# LM2596.net
KiCad netlist of a schematic drawn in Altium Designer
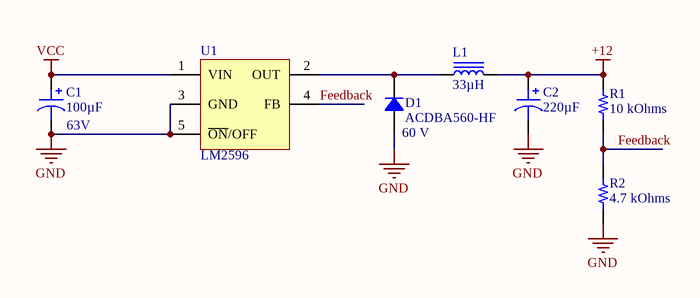
[diagram p0: LM2596.SchDoc]

(export (version "E")
  (design (tool "Eeschema 10.0.6"))
  (components
    (comp (ref "C1")
      (value "100µF")
      (footprint "CAP TH ALUM ELEC D8.00mm S3.50mm H12.50mm")
      (description "CAP ALUM 100UF 20% 63V RADIAL")
      (fields
        (field (name "PART NUMBER") "ECA-1JM101")
        (field (name "MANUFACTURER") "Panasonic Electronic Components")
        (field (name "VOLTAGE - RATED") "63V")
      )
      (libsource (lib "Celestial Altium Library - altium_library") (part "Polarised Capacitor"))
    )
    (comp (ref "C2")
      (value "220µF")
      (footprint "CAP TH ALUM ELEC D10.00mm S5.00mm H16.00mm")
      (description "CAP ALUM 220UF 20% 63V RADIAL")
      (fields (field (name "PART NUMBER") "UFW1J221MPD") (field (name "MANUFACTURER") "Nichicon"))
      (libsource (lib "Celestial Altium Library - altium_library") (part "Polarised Capacitor"))
    )
    (comp (ref "D1")
      (value "ACDBA560-HF")
      (footprint "DO214AC SMA")
      (description "DIODE SCHOTTKY 60V 5A DO214AC")
      (fields
        (field (name "MANUFACTURER") "Comchip Technology")
        (field (name "VOLTAGE - DC REVERSE (VR) (MAX)") "60 V")
      )
      (libsource (lib "Celestial Altium Library - altium_library") (part "Diode"))
    )
    (comp (ref "L1")
      (value "33µH")
      (footprint "BOURNS SRR1280")
      (description "FIXED IND 33UH 3.5A 57 MOHM SMD")
      (fields (field (name "PART NUMBER") "SRR1280-330M") (field (name "MANUFACTURER") "Bourns Inc."))
      (libsource (lib "Celestial Altium Library - altium_library") (part "Inductor"))
    )
    (comp (ref "R1")
      (value "10 kOhms")
      (footprint "RES 0805_2012")
      (description "RES 10K OHM 0.1% 1/10W 0805")
      (fields
        (field (name "PART NUMBER") "RNCS0805BKE10K0")
        (field (name "MANUFACTURER") "Stackpole Electronics Inc")
      )
      (libsource (lib "Celestial Altium Library - altium_library") (part "Resistor"))
    )
    (comp (ref "R2")
      (value "4.7 kOhms")
      (footprint "RES 0805_2012")
      (description "RES SMD 4.7K OHM 1% 1/8W 0805")
      (fields (field (name "PART NUMBER") "RC0805FR-074K7P") (field (name "MANUFACTURER") "Yageo"))
      (libsource (lib "Celestial Altium Library - altium_library") (part "Resistor"))
    )
    (comp (ref "U1")
      (value "LM2596")
      (footprint "D2PAK")
      (description "LM2596DSADJG Switching Regulator 3A Adjustable; 1.23 to 37 V; 5-Pin D2PAK")
      (fields
        (field (name "MANUFACTURER") "ON Semiconductor")
        (field (name "MANUFACTURER PART NUMBER") "LM2596DSADJG")
        (field (name "DESIGNED BY") "Burak")
      )
      (libsource (lib "UDEMY_Library") (part "LM2596"))
    )
  )
  (nets
    (net (code "1") (name "+12") (class "Default")
      (node (ref "C2") (pin "1") (pinfunction "1_1") (pintype "passive"))
      (node (ref "L1") (pin "2") (pinfunction "2_2") (pintype "passive"))
      (node (ref "R1") (pin "2") (pinfunction "2_2") (pintype "passive"))
    )
    (net (code "2") (name "/Feedback") (class "Default")
      (node (ref "R1") (pin "1") (pinfunction "1_1") (pintype "passive"))
      (node (ref "R2") (pin "2") (pinfunction "2_2") (pintype "passive"))
      (node (ref "U1") (pin "4") (pinfunction "FB_4") (pintype "passive"))
    )
    (net (code "3") (name "GND") (class "Default")
      (node (ref "C1") (pin "2") (pinfunction "2_2") (pintype "passive"))
      (node (ref "C2") (pin "2") (pinfunction "2_2") (pintype "passive"))
      (node (ref "D1") (pin "1") (pinfunction "1_1") (pintype "passive"))
      (node (ref "R2") (pin "1") (pinfunction "1_1") (pintype "passive"))
      (node (ref "U1") (pin "3") (pinfunction "GND_3") (pintype "passive"))
      (node (ref "U1") (pin "5") (pinfunction "~{ON}/OFF_5") (pintype "passive"))
    )
    (net (code "4") (name "Net-(U1-OUT)") (class "Default")
      (node (ref "D1") (pin "2") (pinfunction "2_2") (pintype "passive"))
      (node (ref "L1") (pin "1") (pinfunction "1_1") (pintype "passive"))
      (node (ref "U1") (pin "2") (pinfunction "OUT_2") (pintype "passive"))
    )
    (net (code "5") (name "VCC") (class "Default")
      (node (ref "C1") (pin "1") (pinfunction "1_1") (pintype "passive"))
      (node (ref "U1") (pin "1") (pinfunction "VIN_1") (pintype "passive"))
    )
  )
)
